# easyeda_file.net
KiCad netlist of a schematic drawn in EasyEDA
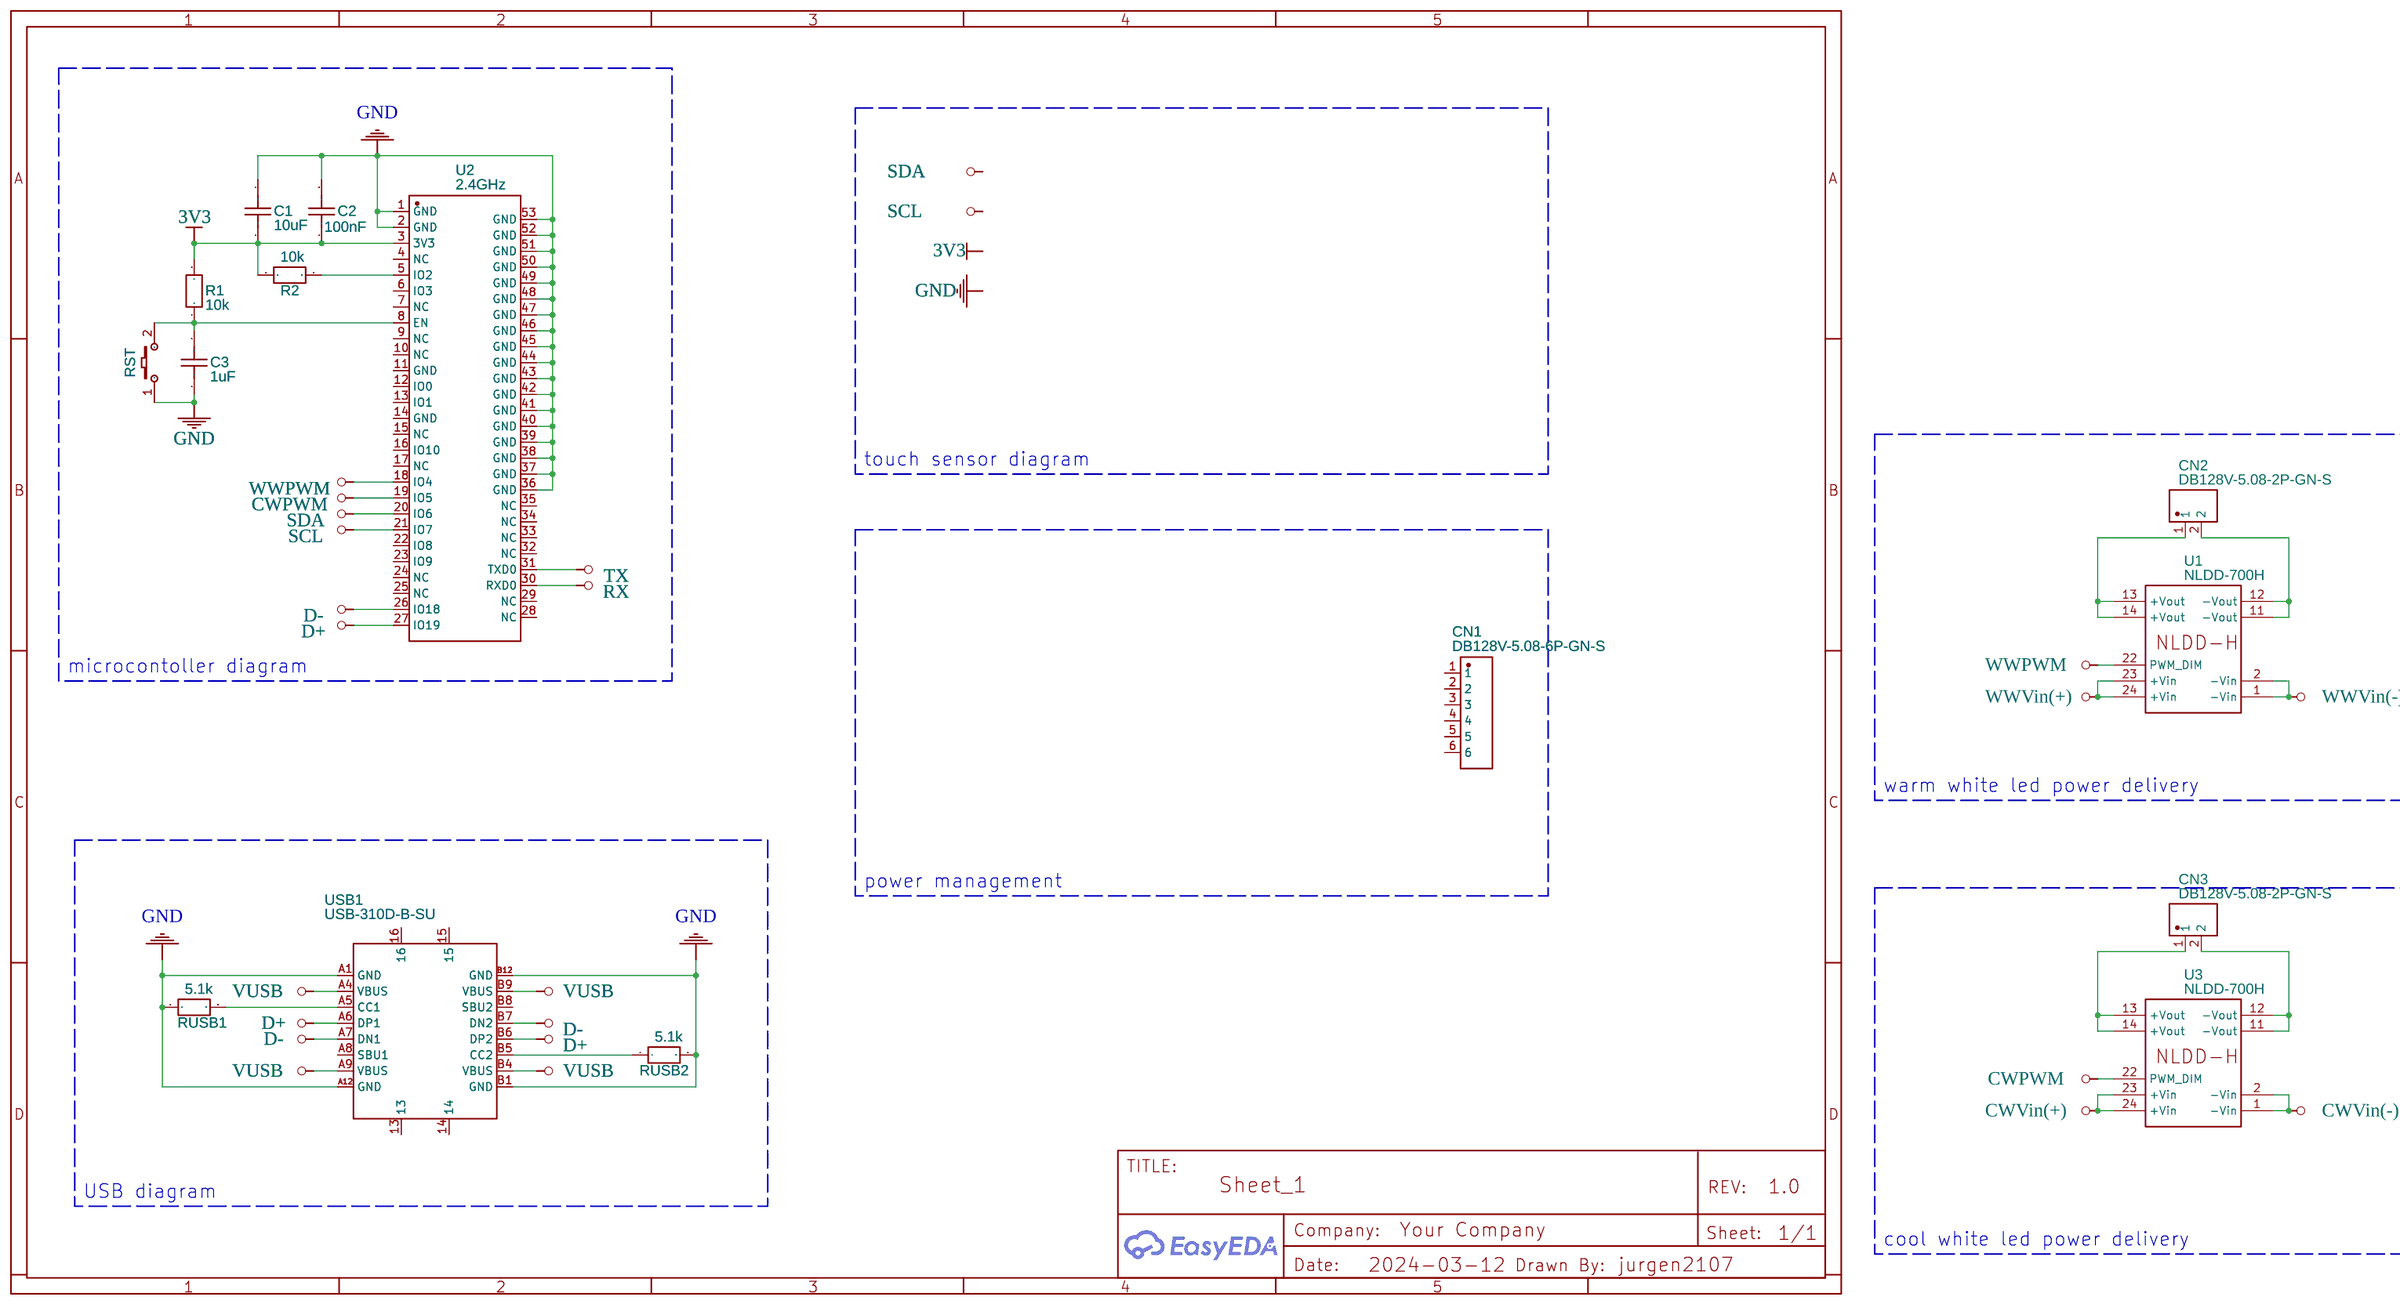
[diagram p0: schematic sheet]

(export (version "E")
  (design (tool "Eeschema 10.0.6"))
  (components
    (comp (ref "C1") (value "10uF") (libsource (lib "") (part "C_0603_US")))
    (comp (ref "C2") (value "100nF") (libsource (lib "") (part "C_0603_US")))
    (comp (ref "C3") (value "1uF") (libsource (lib "") (part "C_0603_US")))
    (comp (ref "CN1")
      (value "DB128V-5.08-6P-GN-S")
      (fields (field (name "Manufacturer") "DIBO(地博电气)"))
      (libsource (lib "") (part "DB128V-5.08-6P-GN-S"))
    )
    (comp (ref "CN2")
      (value "DB128V-5.08-2P-GN-S")
      (fields (field (name "Manufacturer") "DIBO(地博电气)"))
      (libsource (lib "") (part "DB128V-5.08-2P-GN-S"))
    )
    (comp (ref "CN3")
      (value "DB128V-5.08-2P-GN-S")
      (fields (field (name "Manufacturer") "DIBO(地博电气)"))
      (libsource (lib "") (part "DB128V-5.08-2P-GN-S"))
    )
    (comp (ref "R1") (value "10k") (libsource (lib "") (part "R_0603_EU")))
    (comp (ref "R2") (value "10k") (libsource (lib "") (part "R_0603_EU_2")))
    (comp (ref "RST")
      (value "K2-3.6×6.1_SMD")
      (fields (field (name "Manufacturer Part") "K2-1107ST-A4SW-06"))
      (libsource (lib "") (part "K2-3.6×6.1_SMD"))
    )
    (comp (ref "RUSB1") (value "5.1k") (libsource (lib "") (part "R_0603_EU_1")))
    (comp (ref "RUSB2") (value "5.1k") (libsource (lib "") (part "R_0603_EU_1")))
    (comp (ref "U1")
      (value "NLDD-700H")
      (fields (field (name "Manufacturer Part") "709-NLDD-700H") (field (name "Manufacturer") "MEAN WELL"))
      (libsource (lib "") (part "NLDD-700H"))
    )
    (comp (ref "U2")
      (value "2.4GHz")
      (fields
        (field (name "Manufacturer Part") "ESP32-C3-MINI-1-H4")
        (field (name "Manufacturer") "ESPRESSIF(乐鑫)")
      )
      (libsource (lib "") (part "ESP32-C3-MINI-1-H4(4MB)"))
    )
    (comp (ref "U3")
      (value "NLDD-700H")
      (fields (field (name "Manufacturer Part") "709-NLDD-700H") (field (name "Manufacturer") "MEAN WELL"))
      (libsource (lib "") (part "NLDD-700H"))
    )
    (comp (ref "USB1")
      (value "USB-310D-B-SU")
      (fields (field (name "Manufacturer") "HOOYA(皓宇电子)"))
      (libsource (lib "") (part "USB-310D-B-SU"))
    )
  )
  (nets
    (net (code "1") (name "3V3") (class "Default")
      (node (ref "C1") (pin "1") (pinfunction "1_1") (pintype "unspecified"))
      (node (ref "C2") (pin "1") (pinfunction "1_1") (pintype "unspecified"))
      (node (ref "R1") (pin "2") (pinfunction "2_2") (pintype "unspecified"))
      (node (ref "R2") (pin "1") (pinfunction "1_1") (pintype "unspecified"))
      (node (ref "U2") (pin "3") (pinfunction "3V3_3") (pintype "unspecified"))
    )
    (net (code "2") (name "CWPWM") (class "Default")
      (node (ref "U2") (pin "19") (pinfunction "IO5_19") (pintype "unspecified"))
      (node (ref "U3") (pin "22") (pinfunction "PWM_DIM_22") (pintype "unspecified"))
    )
    (net (code "3") (name "CWVin(+)") (class "Default")
      (node (ref "U3") (pin "23") (pinfunction "+Vin_23") (pintype "unspecified"))
      (node (ref "U3") (pin "24") (pinfunction "+Vin_24") (pintype "unspecified"))
    )
    (net (code "4") (name "CWVin(-)") (class "Default")
      (node (ref "U3") (pin "1") (pinfunction "-Vin_1") (pintype "unspecified"))
      (node (ref "U3") (pin "2") (pinfunction "-Vin_2") (pintype "unspecified"))
    )
    (net (code "5") (name "D+") (class "Default")
      (node (ref "U2") (pin "27") (pinfunction "IO19_27") (pintype "unspecified"))
      (node (ref "USB1") (pin "A6") (pinfunction "DP1_A6") (pintype "unspecified"))
      (node (ref "USB1") (pin "B6") (pinfunction "DP2_B6") (pintype "unspecified"))
    )
    (net (code "6") (name "D-") (class "Default")
      (node (ref "U2") (pin "26") (pinfunction "IO18_26") (pintype "unspecified"))
      (node (ref "USB1") (pin "A7") (pinfunction "DN1_A7") (pintype "unspecified"))
      (node (ref "USB1") (pin "B7") (pinfunction "DN2_B7") (pintype "unspecified"))
    )
    (net (code "7") (name "GND") (class "Default")
      (node (ref "C1") (pin "2") (pinfunction "2_2") (pintype "unspecified"))
      (node (ref "C2") (pin "2") (pinfunction "2_2") (pintype "unspecified"))
      (node (ref "C3") (pin "1") (pinfunction "1_1") (pintype "unspecified"))
      (node (ref "RST") (pin "1") (pinfunction "1_1") (pintype "unspecified"))
      (node (ref "RUSB1") (pin "1") (pinfunction "1_1") (pintype "unspecified"))
      (node (ref "RUSB2") (pin "2") (pinfunction "2_2") (pintype "unspecified"))
      (node (ref "U2") (pin "1") (pinfunction "GND_1") (pintype "unspecified"))
      (node (ref "U2") (pin "2") (pinfunction "GND_2") (pintype "unspecified"))
      (node (ref "U2") (pin "36") (pinfunction "GND_36") (pintype "unspecified"))
      (node (ref "U2") (pin "37") (pinfunction "GND_37") (pintype "unspecified"))
      (node (ref "U2") (pin "38") (pinfunction "GND_38") (pintype "unspecified"))
      (node (ref "U2") (pin "39") (pinfunction "GND_39") (pintype "unspecified"))
      (node (ref "U2") (pin "40") (pinfunction "GND_40") (pintype "unspecified"))
      (node (ref "U2") (pin "41") (pinfunction "GND_41") (pintype "unspecified"))
      (node (ref "U2") (pin "42") (pinfunction "GND_42") (pintype "unspecified"))
      (node (ref "U2") (pin "43") (pinfunction "GND_43") (pintype "unspecified"))
      (node (ref "U2") (pin "44") (pinfunction "GND_44") (pintype "unspecified"))
      (node (ref "U2") (pin "45") (pinfunction "GND_45") (pintype "unspecified"))
      (node (ref "U2") (pin "46") (pinfunction "GND_46") (pintype "unspecified"))
      (node (ref "U2") (pin "47") (pinfunction "GND_47") (pintype "unspecified"))
      (node (ref "U2") (pin "48") (pinfunction "GND_48") (pintype "unspecified"))
      (node (ref "U2") (pin "49") (pinfunction "GND_49") (pintype "unspecified"))
      (node (ref "U2") (pin "50") (pinfunction "GND_50") (pintype "unspecified"))
      (node (ref "U2") (pin "51") (pinfunction "GND_51") (pintype "unspecified"))
      (node (ref "U2") (pin "52") (pinfunction "GND_52") (pintype "unspecified"))
      (node (ref "U2") (pin "53") (pinfunction "GND_53") (pintype "unspecified"))
      (node (ref "USB1") (pin "A1") (pinfunction "GND_A1") (pintype "unspecified"))
      (node (ref "USB1") (pin "A12") (pinfunction "GND_A12") (pintype "unspecified"))
      (node (ref "USB1") (pin "B1") (pinfunction "GND_B1") (pintype "unspecified"))
      (node (ref "USB1") (pin "B12") (pinfunction "GND_B12") (pintype "unspecified"))
    )
    (net (code "8") (name "Net-(CN2-Pad1)") (class "Default")
      (node (ref "CN2") (pin "1") (pinfunction "1_1") (pintype "unspecified"))
      (node (ref "U1") (pin "13") (pinfunction "+Vout_13") (pintype "unspecified"))
      (node (ref "U1") (pin "14") (pinfunction "+Vout_14") (pintype "unspecified"))
    )
    (net (code "9") (name "Net-(CN2-Pad2)") (class "Default")
      (node (ref "CN2") (pin "2") (pinfunction "2_2") (pintype "unspecified"))
      (node (ref "U1") (pin "11") (pinfunction "-Vout_11") (pintype "unspecified"))
      (node (ref "U1") (pin "12") (pinfunction "-Vout_12") (pintype "unspecified"))
    )
    (net (code "10") (name "Net-(CN3-Pad1)") (class "Default")
      (node (ref "CN3") (pin "1") (pinfunction "1_1") (pintype "unspecified"))
      (node (ref "U3") (pin "13") (pinfunction "+Vout_13") (pintype "unspecified"))
      (node (ref "U3") (pin "14") (pinfunction "+Vout_14") (pintype "unspecified"))
    )
    (net (code "11") (name "Net-(CN3-Pad2)") (class "Default")
      (node (ref "CN3") (pin "2") (pinfunction "2_2") (pintype "unspecified"))
      (node (ref "U3") (pin "11") (pinfunction "-Vout_11") (pintype "unspecified"))
      (node (ref "U3") (pin "12") (pinfunction "-Vout_12") (pintype "unspecified"))
    )
    (net (code "12") (name "Net-(U2-EN)") (class "Default")
      (node (ref "C3") (pin "2") (pinfunction "2_2") (pintype "unspecified"))
      (node (ref "R1") (pin "1") (pinfunction "1_1") (pintype "unspecified"))
      (node (ref "RST") (pin "2") (pinfunction "2_2") (pintype "unspecified"))
      (node (ref "U2") (pin "8") (pinfunction "EN_8") (pintype "unspecified"))
    )
    (net (code "13") (name "Net-(U2-IO2)") (class "Default")
      (node (ref "R2") (pin "2") (pinfunction "2_2") (pintype "unspecified"))
      (node (ref "U2") (pin "5") (pinfunction "IO2_5") (pintype "unspecified"))
    )
    (net (code "14") (name "Net-(USB1-CC1)") (class "Default")
      (node (ref "RUSB1") (pin "2") (pinfunction "2_2") (pintype "unspecified"))
      (node (ref "USB1") (pin "A5") (pinfunction "CC1_A5") (pintype "unspecified"))
    )
    (net (code "15") (name "Net-(USB1-CC2)") (class "Default")
      (node (ref "RUSB2") (pin "1") (pinfunction "1_1") (pintype "unspecified"))
      (node (ref "USB1") (pin "B5") (pinfunction "CC2_B5") (pintype "unspecified"))
    )
    (net (code "16") (name "RX") (class "Default")
      (node (ref "U2") (pin "30") (pinfunction "RXD0_30") (pintype "unspecified"))
    )
    (net (code "17") (name "SCL") (class "Default")
      (node (ref "U2") (pin "21") (pinfunction "IO7_21") (pintype "unspecified"))
    )
    (net (code "18") (name "SDA") (class "Default")
      (node (ref "U2") (pin "20") (pinfunction "IO6_20") (pintype "unspecified"))
    )
    (net (code "19") (name "TX") (class "Default")
      (node (ref "U2") (pin "31") (pinfunction "TXD0_31") (pintype "unspecified"))
    )
    (net (code "20") (name "VUSB") (class "Default")
      (node (ref "USB1") (pin "A4") (pinfunction "VBUS_A4") (pintype "unspecified"))
      (node (ref "USB1") (pin "A9") (pinfunction "VBUS_A9") (pintype "unspecified"))
      (node (ref "USB1") (pin "B4") (pinfunction "VBUS_B4") (pintype "unspecified"))
      (node (ref "USB1") (pin "B9") (pinfunction "VBUS_B9") (pintype "unspecified"))
    )
    (net (code "21") (name "WWPWM") (class "Default")
      (node (ref "U1") (pin "22") (pinfunction "PWM_DIM_22") (pintype "unspecified"))
      (node (ref "U2") (pin "18") (pinfunction "IO4_18") (pintype "unspecified"))
    )
    (net (code "22") (name "WWVin(+)") (class "Default")
      (node (ref "U1") (pin "23") (pinfunction "+Vin_23") (pintype "unspecified"))
      (node (ref "U1") (pin "24") (pinfunction "+Vin_24") (pintype "unspecified"))
    )
    (net (code "23") (name "WWVin(-)") (class "Default")
      (node (ref "U1") (pin "1") (pinfunction "-Vin_1") (pintype "unspecified"))
      (node (ref "U1") (pin "2") (pinfunction "-Vin_2") (pintype "unspecified"))
    )
    (net (code "24") (name "unconnected-(CN1-Pad1)") (class "Default")
      (node (ref "CN1") (pin "1") (pinfunction "1_1") (pintype "unspecified"))
    )
    (net (code "25") (name "unconnected-(CN1-Pad2)") (class "Default")
      (node (ref "CN1") (pin "2") (pinfunction "2_2") (pintype "unspecified"))
    )
    (net (code "26") (name "unconnected-(CN1-Pad3)") (class "Default")
      (node (ref "CN1") (pin "3") (pinfunction "3_3") (pintype "unspecified"))
    )
    (net (code "27") (name "unconnected-(CN1-Pad4)") (class "Default")
      (node (ref "CN1") (pin "4") (pinfunction "4_4") (pintype "unspecified"))
    )
    (net (code "28") (name "unconnected-(CN1-Pad5)") (class "Default")
      (node (ref "CN1") (pin "5") (pinfunction "5_5") (pintype "unspecified"))
    )
    (net (code "29") (name "unconnected-(CN1-Pad6)") (class "Default")
      (node (ref "CN1") (pin "6") (pinfunction "6_6") (pintype "unspecified"))
    )
    (net (code "30") (name "unconnected-(U2-GND-Pad11)") (class "Default")
      (node (ref "U2") (pin "11") (pinfunction "GND_11") (pintype "unspecified"))
    )
    (net (code "31") (name "unconnected-(U2-GND-Pad14)") (class "Default")
      (node (ref "U2") (pin "14") (pinfunction "GND_14") (pintype "unspecified"))
    )
    (net (code "32") (name "unconnected-(U2-IO0-Pad12)") (class "Default")
      (node (ref "U2") (pin "12") (pinfunction "IO0_12") (pintype "unspecified"))
    )
    (net (code "33") (name "unconnected-(U2-IO1-Pad13)") (class "Default")
      (node (ref "U2") (pin "13") (pinfunction "IO1_13") (pintype "unspecified"))
    )
    (net (code "34") (name "unconnected-(U2-IO3-Pad6)") (class "Default")
      (node (ref "U2") (pin "6") (pinfunction "IO3_6") (pintype "unspecified"))
    )
    (net (code "35") (name "unconnected-(U2-IO8-Pad22)") (class "Default")
      (node (ref "U2") (pin "22") (pinfunction "IO8_22") (pintype "unspecified"))
    )
    (net (code "36") (name "unconnected-(U2-IO9-Pad23)") (class "Default")
      (node (ref "U2") (pin "23") (pinfunction "IO9_23") (pintype "unspecified"))
    )
    (net (code "37") (name "unconnected-(U2-IO10-Pad16)") (class "Default")
      (node (ref "U2") (pin "16") (pinfunction "IO10_16") (pintype "unspecified"))
    )
    (net (code "38") (name "unconnected-(U2-NC-Pad4)") (class "Default")
      (node (ref "U2") (pin "4") (pinfunction "NC_4") (pintype "unspecified"))
    )
    (net (code "39") (name "unconnected-(U2-NC-Pad7)") (class "Default")
      (node (ref "U2") (pin "7") (pinfunction "NC_7") (pintype "unspecified"))
    )
    (net (code "40") (name "unconnected-(U2-NC-Pad9)") (class "Default")
      (node (ref "U2") (pin "9") (pinfunction "NC_9") (pintype "unspecified"))
    )
    (net (code "41") (name "unconnected-(U2-NC-Pad10)") (class "Default")
      (node (ref "U2") (pin "10") (pinfunction "NC_10") (pintype "unspecified"))
    )
    (net (code "42") (name "unconnected-(U2-NC-Pad15)") (class "Default")
      (node (ref "U2") (pin "15") (pinfunction "NC_15") (pintype "unspecified"))
    )
    (net (code "43") (name "unconnected-(U2-NC-Pad17)") (class "Default")
      (node (ref "U2") (pin "17") (pinfunction "NC_17") (pintype "unspecified"))
    )
    (net (code "44") (name "unconnected-(U2-NC-Pad24)") (class "Default")
      (node (ref "U2") (pin "24") (pinfunction "NC_24") (pintype "unspecified"))
    )
    (net (code "45") (name "unconnected-(U2-NC-Pad25)") (class "Default")
      (node (ref "U2") (pin "25") (pinfunction "NC_25") (pintype "unspecified"))
    )
    (net (code "46") (name "unconnected-(U2-NC-Pad28)") (class "Default")
      (node (ref "U2") (pin "28") (pinfunction "NC_28") (pintype "unspecified"))
    )
    (net (code "47") (name "unconnected-(U2-NC-Pad29)") (class "Default")
      (node (ref "U2") (pin "29") (pinfunction "NC_29") (pintype "unspecified"))
    )
    (net (code "48") (name "unconnected-(U2-NC-Pad32)") (class "Default")
      (node (ref "U2") (pin "32") (pinfunction "NC_32") (pintype "unspecified"))
    )
    (net (code "49") (name "unconnected-(U2-NC-Pad33)") (class "Default")
      (node (ref "U2") (pin "33") (pinfunction "NC_33") (pintype "unspecified"))
    )
    (net (code "50") (name "unconnected-(U2-NC-Pad34)") (class "Default")
      (node (ref "U2") (pin "34") (pinfunction "NC_34") (pintype "unspecified"))
    )
    (net (code "51") (name "unconnected-(U2-NC-Pad35)") (class "Default")
      (node (ref "U2") (pin "35") (pinfunction "NC_35") (pintype "unspecified"))
    )
    (net (code "52") (name "unconnected-(USB1-Pad13)") (class "Default")
      (node (ref "USB1") (pin "13") (pinfunction "13_13") (pintype "unspecified"))
    )
    (net (code "53") (name "unconnected-(USB1-Pad14)") (class "Default")
      (node (ref "USB1") (pin "14") (pinfunction "14_14") (pintype "unspecified"))
    )
    (net (code "54") (name "unconnected-(USB1-Pad15)") (class "Default")
      (node (ref "USB1") (pin "15") (pinfunction "15_15") (pintype "unspecified"))
    )
    (net (code "55") (name "unconnected-(USB1-Pad16)") (class "Default")
      (node (ref "USB1") (pin "16") (pinfunction "16_16") (pintype "unspecified"))
    )
    (net (code "56") (name "unconnected-(USB1-SBU1-PadA8)") (class "Default")
      (node (ref "USB1") (pin "A8") (pinfunction "SBU1_A8") (pintype "unspecified"))
    )
    (net (code "57") (name "unconnected-(USB1-SBU2-PadB8)") (class "Default")
      (node (ref "USB1") (pin "B8") (pinfunction "SBU2_B8") (pintype "unspecified"))
    )
  )
)
